# board.net
KiCad netlist of a schematic drawn in EAGLE
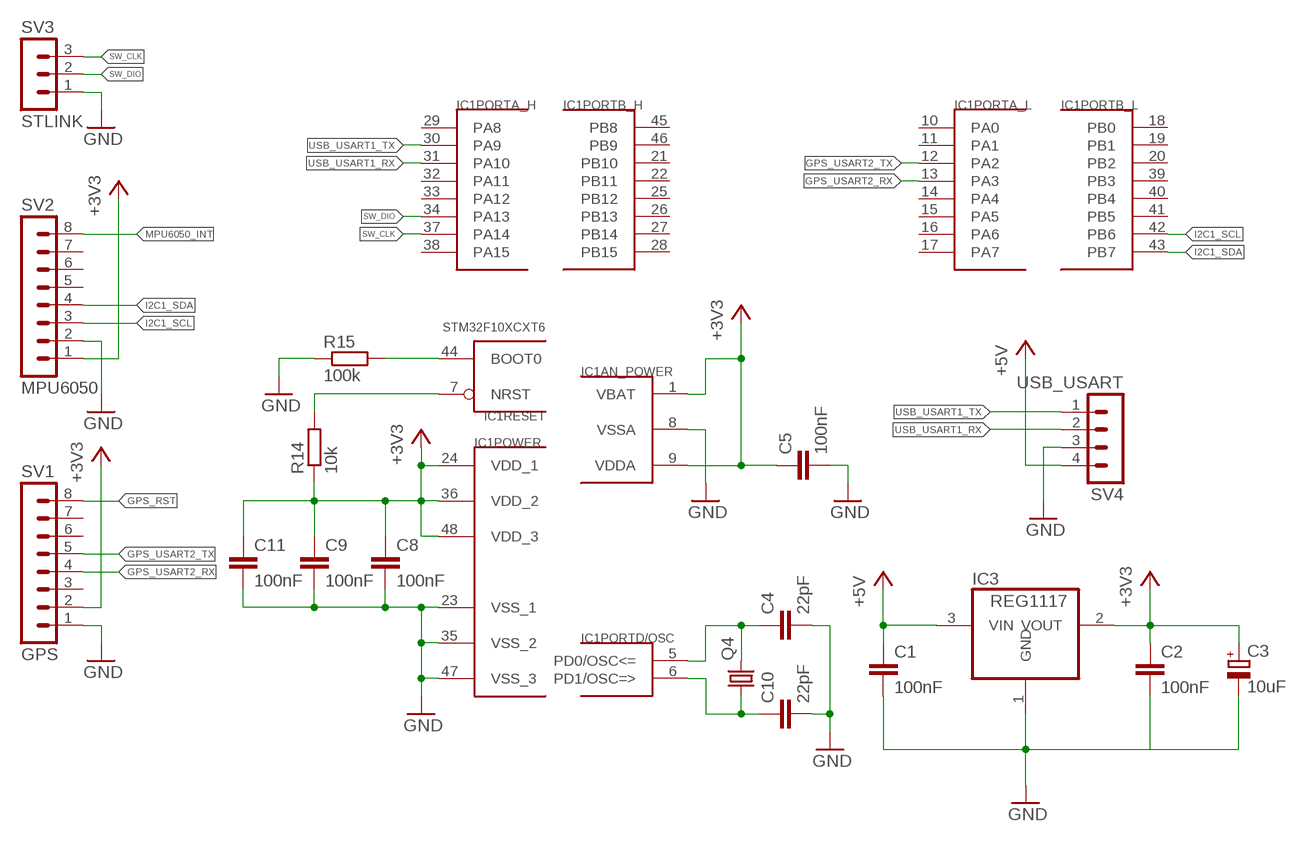
[diagram p0: schematic, sheet 1]

(export (version "E")
  (design (tool "Eeschema 10.0.6"))
  (components
    (comp (ref "C1")
      (value "100nF")
      (footprint "eagle-import:C0805")
      (libsource (lib "eagle-import") (part "C-EUC0805"))
    )
    (comp (ref "C2")
      (value "100nF")
      (footprint "eagle-import:C0805")
      (libsource (lib "eagle-import") (part "C-EUC0805"))
    )
    (comp (ref "C3")
      (value "10uF")
      (footprint "eagle-import:C_6032-28W")
      (libsource (lib "eagle-import") (part "CPOL-EUC/6032-28W"))
    )
    (comp (ref "C4")
      (value "22pF")
      (footprint "eagle-import:C0805")
      (libsource (lib "eagle-import") (part "C-EUC0805"))
    )
    (comp (ref "C5")
      (value "100nF")
      (footprint "eagle-import:C0603")
      (libsource (lib "eagle-import") (part "C-EUC0603"))
    )
    (comp (ref "C8")
      (value "100nF")
      (footprint "eagle-import:C0805")
      (libsource (lib "eagle-import") (part "C-EUC0805"))
    )
    (comp (ref "C9")
      (value "100nF")
      (footprint "eagle-import:C0805")
      (libsource (lib "eagle-import") (part "C-EUC0805"))
    )
    (comp (ref "C10")
      (value "22pF")
      (footprint "eagle-import:C0805")
      (libsource (lib "eagle-import") (part "C-EUC0805"))
    )
    (comp (ref "C11")
      (value "100nF")
      (footprint "eagle-import:C0805")
      (libsource (lib "eagle-import") (part "C-EUC0805"))
    )
    (comp (ref "IC1")
      (value "STM32F10XCXT6")
      (footprint "eagle-import:TQFP48")
      (libsource (lib "eagle-import") (part "STM32F10XCXT6"))
    )
    (comp (ref "IC3")
      (value "REG1117")
      (footprint "eagle-import:SOT223")
      (libsource (lib "eagle-import") (part "REG1117"))
    )
    (comp (ref "Q4")
      (value "CRYSTALHC49UP")
      (footprint "eagle-import:HC49UP")
      (libsource (lib "eagle-import") (part "CRYSTALHC49UP"))
    )
    (comp (ref "R14")
      (value "10k")
      (footprint "eagle-import:M0805")
      (libsource (lib "eagle-import") (part "R-EU_M0805"))
    )
    (comp (ref "R15")
      (value "100k")
      (footprint "eagle-import:M0805")
      (libsource (lib "eagle-import") (part "R-EU_M0805"))
    )
    (comp (ref "SV1")
      (value "GPS")
      (footprint "eagle-import:MA08-1")
      (libsource (lib "eagle-import") (part "MA08-1"))
    )
    (comp (ref "SV2")
      (value "MPU6050")
      (footprint "eagle-import:MA08-1")
      (libsource (lib "eagle-import") (part "MA08-1"))
    )
    (comp (ref "SV3")
      (value "STLINK")
      (footprint "eagle-import:MA03-1")
      (libsource (lib "eagle-import") (part "MA03-1"))
    )
    (comp (ref "SV4")
      (value "USB_USART")
      (footprint "eagle-import:MA04-1")
      (libsource (lib "eagle-import") (part "MA04-1"))
    )
  )
  (nets
    (net (code "1") (name "+3V3") (class "Default")
      (node (ref "C11") (pin "1") (pinfunction "1_1") (pintype "passive"))
      (node (ref "C2") (pin "1") (pinfunction "1_1") (pintype "passive"))
      (node (ref "C3") (pin "+") (pinfunction "+_+") (pintype "passive"))
      (node (ref "C5") (pin "1") (pinfunction "1_1") (pintype "passive"))
      (node (ref "C8") (pin "1") (pinfunction "1_1") (pintype "passive"))
      (node (ref "C9") (pin "1") (pinfunction "1_1") (pintype "passive"))
      (node (ref "IC1") (pin "1") (pinfunction "VBAT_1") (pintype "power_in"))
      (node (ref "IC1") (pin "24") (pinfunction "VDD_1_24") (pintype "power_in"))
      (node (ref "IC1") (pin "36") (pinfunction "VDD_2_36") (pintype "power_in"))
      (node (ref "IC1") (pin "48") (pinfunction "VDD_3_48") (pintype "power_in"))
      (node (ref "IC1") (pin "9") (pinfunction "VDDA_9") (pintype "power_in"))
      (node (ref "IC3") (pin "2") (pinfunction "VOUT_2") (pintype "output"))
      (node (ref "R14") (pin "1") (pinfunction "1_1") (pintype "passive"))
      (node (ref "SV1") (pin "2") (pinfunction "2_2") (pintype "passive"))
      (node (ref "SV2") (pin "1") (pinfunction "1_1") (pintype "passive"))
    )
    (net (code "2") (name "+5V") (class "Default")
      (node (ref "C1") (pin "1") (pinfunction "1_1") (pintype "passive"))
      (node (ref "IC3") (pin "3") (pinfunction "VIN_3") (pintype "input"))
      (node (ref "SV4") (pin "4") (pinfunction "4_4") (pintype "passive"))
    )
    (net (code "3") (name "GND") (class "Default")
      (node (ref "C1") (pin "2") (pinfunction "2_2") (pintype "passive"))
      (node (ref "C10") (pin "2") (pinfunction "2_2") (pintype "passive"))
      (node (ref "C11") (pin "2") (pinfunction "2_2") (pintype "passive"))
      (node (ref "C2") (pin "2") (pinfunction "2_2") (pintype "passive"))
      (node (ref "C3") (pin "-") (pinfunction "-_-") (pintype "passive"))
      (node (ref "C4") (pin "2") (pinfunction "2_2") (pintype "passive"))
      (node (ref "C5") (pin "2") (pinfunction "2_2") (pintype "passive"))
      (node (ref "C8") (pin "2") (pinfunction "2_2") (pintype "passive"))
      (node (ref "C9") (pin "2") (pinfunction "2_2") (pintype "passive"))
      (node (ref "IC1") (pin "23") (pinfunction "VSS_1_23") (pintype "power_in"))
      (node (ref "IC1") (pin "35") (pinfunction "VSS_2_35") (pintype "power_in"))
      (node (ref "IC1") (pin "47") (pinfunction "VSS_3_47") (pintype "power_in"))
      (node (ref "IC1") (pin "8") (pinfunction "VSSA_8") (pintype "power_in"))
      (node (ref "IC3") (pin "1") (pinfunction "GND_1") (pintype "power_in"))
      (node (ref "R15") (pin "1") (pinfunction "1_1") (pintype "passive"))
      (node (ref "SV1") (pin "1") (pinfunction "1_1") (pintype "passive"))
      (node (ref "SV2") (pin "2") (pinfunction "2_2") (pintype "passive"))
      (node (ref "SV3") (pin "1") (pinfunction "1_1") (pintype "passive"))
      (node (ref "SV4") (pin "3") (pinfunction "3_3") (pintype "passive"))
    )
    (net (code "4") (name "GPS_RST") (class "Default")
      (node (ref "SV1") (pin "8") (pinfunction "8_8") (pintype "passive"))
    )
    (net (code "5") (name "GPS_USART2_RX") (class "Default")
      (node (ref "IC1") (pin "13") (pinfunction "PA3_13") (pintype "bidirectional"))
      (node (ref "SV1") (pin "4") (pinfunction "4_4") (pintype "passive"))
    )
    (net (code "6") (name "GPS_USART2_TX") (class "Default")
      (node (ref "IC1") (pin "12") (pinfunction "PA2_12") (pintype "bidirectional"))
      (node (ref "SV1") (pin "5") (pinfunction "5_5") (pintype "passive"))
    )
    (net (code "7") (name "I2C1_SCL") (class "Default")
      (node (ref "IC1") (pin "42") (pinfunction "PB6_42") (pintype "bidirectional"))
      (node (ref "SV2") (pin "3") (pinfunction "3_3") (pintype "passive"))
    )
    (net (code "8") (name "I2C1_SDA") (class "Default")
      (node (ref "IC1") (pin "43") (pinfunction "PB7_43") (pintype "bidirectional"))
      (node (ref "SV2") (pin "4") (pinfunction "4_4") (pintype "passive"))
    )
    (net (code "9") (name "MPU6050_INT") (class "Default")
      (node (ref "SV2") (pin "8") (pinfunction "8_8") (pintype "passive"))
    )
    (net (code "10") (name "Net-(IC1G-PD0{slash}OSC<=)") (class "Default")
      (node (ref "C4") (pin "1") (pinfunction "1_1") (pintype "passive"))
      (node (ref "IC1") (pin "5") (pinfunction "PD0/OSC<=_5") (pintype "bidirectional"))
      (node (ref "Q4") (pin "2") (pinfunction "2_2") (pintype "passive"))
    )
    (net (code "11") (name "Net-(IC1G-PD1{slash}OSC=>)") (class "Default")
      (node (ref "C10") (pin "1") (pinfunction "1_1") (pintype "passive"))
      (node (ref "IC1") (pin "6") (pinfunction "PD1/OSC=>_6") (pintype "bidirectional"))
      (node (ref "Q4") (pin "1") (pinfunction "1_1") (pintype "passive"))
    )
    (net (code "12") (name "Net-(IC1I-BOOT0)") (class "Default")
      (node (ref "IC1") (pin "44") (pinfunction "BOOT0_44") (pintype "input"))
      (node (ref "R15") (pin "2") (pinfunction "2_2") (pintype "passive"))
    )
    (net (code "13") (name "Net-(IC1I-NRST)") (class "Default")
      (node (ref "IC1") (pin "7") (pinfunction "NRST_7") (pintype "input"))
      (node (ref "R14") (pin "2") (pinfunction "2_2") (pintype "passive"))
    )
    (net (code "14") (name "SW_CLK") (class "Default")
      (node (ref "IC1") (pin "37") (pinfunction "PA14_37") (pintype "bidirectional"))
      (node (ref "SV3") (pin "3") (pinfunction "3_3") (pintype "passive"))
    )
    (net (code "15") (name "SW_DIO") (class "Default")
      (node (ref "IC1") (pin "34") (pinfunction "PA13_34") (pintype "bidirectional"))
      (node (ref "SV3") (pin "2") (pinfunction "2_2") (pintype "passive"))
    )
    (net (code "16") (name "USB_USART1_RX") (class "Default")
      (node (ref "IC1") (pin "31") (pinfunction "PA10_31") (pintype "bidirectional"))
      (node (ref "SV4") (pin "2") (pinfunction "2_2") (pintype "passive"))
    )
    (net (code "17") (name "USB_USART1_TX") (class "Default")
      (node (ref "IC1") (pin "30") (pinfunction "PA9_30") (pintype "bidirectional"))
      (node (ref "SV4") (pin "1") (pinfunction "1_1") (pintype "passive"))
    )
    (net (code "18") (name "unconnected-(IC1B-PA8-Pad29)") (class "Default")
      (node (ref "IC1") (pin "29") (pinfunction "PA8_29") (pintype "bidirectional"))
    )
    (net (code "19") (name "unconnected-(IC1B-PA11-Pad32)") (class "Default")
      (node (ref "IC1") (pin "32") (pinfunction "PA11_32") (pintype "bidirectional"))
    )
    (net (code "20") (name "unconnected-(IC1B-PA12-Pad33)") (class "Default")
      (node (ref "IC1") (pin "33") (pinfunction "PA12_33") (pintype "bidirectional"))
    )
    (net (code "21") (name "unconnected-(IC1B-PA15-Pad38)") (class "Default")
      (node (ref "IC1") (pin "38") (pinfunction "PA15_38") (pintype "bidirectional"))
    )
    (net (code "22") (name "unconnected-(IC1C-PA0-Pad10)") (class "Default")
      (node (ref "IC1") (pin "10") (pinfunction "PA0_10") (pintype "bidirectional"))
    )
    (net (code "23") (name "unconnected-(IC1C-PA1-Pad11)") (class "Default")
      (node (ref "IC1") (pin "11") (pinfunction "PA1_11") (pintype "bidirectional"))
    )
    (net (code "24") (name "unconnected-(IC1C-PA4-Pad14)") (class "Default")
      (node (ref "IC1") (pin "14") (pinfunction "PA4_14") (pintype "bidirectional"))
    )
    (net (code "25") (name "unconnected-(IC1C-PA5-Pad15)") (class "Default")
      (node (ref "IC1") (pin "15") (pinfunction "PA5_15") (pintype "bidirectional"))
    )
    (net (code "26") (name "unconnected-(IC1C-PA6-Pad16)") (class "Default")
      (node (ref "IC1") (pin "16") (pinfunction "PA6_16") (pintype "bidirectional"))
    )
    (net (code "27") (name "unconnected-(IC1C-PA7-Pad17)") (class "Default")
      (node (ref "IC1") (pin "17") (pinfunction "PA7_17") (pintype "bidirectional"))
    )
    (net (code "28") (name "unconnected-(IC1D-PB8-Pad45)") (class "Default")
      (node (ref "IC1") (pin "45") (pinfunction "PB8_45") (pintype "bidirectional"))
    )
    (net (code "29") (name "unconnected-(IC1D-PB9-Pad46)") (class "Default")
      (node (ref "IC1") (pin "46") (pinfunction "PB9_46") (pintype "bidirectional"))
    )
    (net (code "30") (name "unconnected-(IC1D-PB10-Pad21)") (class "Default")
      (node (ref "IC1") (pin "21") (pinfunction "PB10_21") (pintype "bidirectional"))
    )
    (net (code "31") (name "unconnected-(IC1D-PB11-Pad22)") (class "Default")
      (node (ref "IC1") (pin "22") (pinfunction "PB11_22") (pintype "bidirectional"))
    )
    (net (code "32") (name "unconnected-(IC1D-PB12-Pad25)") (class "Default")
      (node (ref "IC1") (pin "25") (pinfunction "PB12_25") (pintype "bidirectional"))
    )
    (net (code "33") (name "unconnected-(IC1D-PB13-Pad26)") (class "Default")
      (node (ref "IC1") (pin "26") (pinfunction "PB13_26") (pintype "bidirectional"))
    )
    (net (code "34") (name "unconnected-(IC1D-PB14-Pad27)") (class "Default")
      (node (ref "IC1") (pin "27") (pinfunction "PB14_27") (pintype "bidirectional"))
    )
    (net (code "35") (name "unconnected-(IC1D-PB15-Pad28)") (class "Default")
      (node (ref "IC1") (pin "28") (pinfunction "PB15_28") (pintype "bidirectional"))
    )
    (net (code "36") (name "unconnected-(IC1E-PB0-Pad18)") (class "Default")
      (node (ref "IC1") (pin "18") (pinfunction "PB0_18") (pintype "bidirectional"))
    )
    (net (code "37") (name "unconnected-(IC1E-PB1-Pad19)") (class "Default")
      (node (ref "IC1") (pin "19") (pinfunction "PB1_19") (pintype "bidirectional"))
    )
    (net (code "38") (name "unconnected-(IC1E-PB2-Pad20)") (class "Default")
      (node (ref "IC1") (pin "20") (pinfunction "PB2_20") (pintype "bidirectional"))
    )
    (net (code "39") (name "unconnected-(IC1E-PB3-Pad39)") (class "Default")
      (node (ref "IC1") (pin "39") (pinfunction "PB3_39") (pintype "bidirectional"))
    )
    (net (code "40") (name "unconnected-(IC1E-PB4-Pad40)") (class "Default")
      (node (ref "IC1") (pin "40") (pinfunction "PB4_40") (pintype "bidirectional"))
    )
    (net (code "41") (name "unconnected-(IC1E-PB5-Pad41)") (class "Default")
      (node (ref "IC1") (pin "41") (pinfunction "PB5_41") (pintype "bidirectional"))
    )
    (net (code "42") (name "unconnected-(SV1-Pad3)") (class "Default")
      (node (ref "SV1") (pin "3") (pinfunction "3_3") (pintype "passive"))
    )
    (net (code "43") (name "unconnected-(SV1-Pad6)") (class "Default")
      (node (ref "SV1") (pin "6") (pinfunction "6_6") (pintype "passive"))
    )
    (net (code "44") (name "unconnected-(SV1-Pad7)") (class "Default")
      (node (ref "SV1") (pin "7") (pinfunction "7_7") (pintype "passive"))
    )
    (net (code "45") (name "unconnected-(SV2-Pad5)") (class "Default")
      (node (ref "SV2") (pin "5") (pinfunction "5_5") (pintype "passive"))
    )
    (net (code "46") (name "unconnected-(SV2-Pad6)") (class "Default")
      (node (ref "SV2") (pin "6") (pinfunction "6_6") (pintype "passive"))
    )
    (net (code "47") (name "unconnected-(SV2-Pad7)") (class "Default")
      (node (ref "SV2") (pin "7") (pinfunction "7_7") (pintype "passive"))
    )
  )
)
